# ESP-03_Breakout.net
KiCad netlist of a schematic drawn in EAGLE
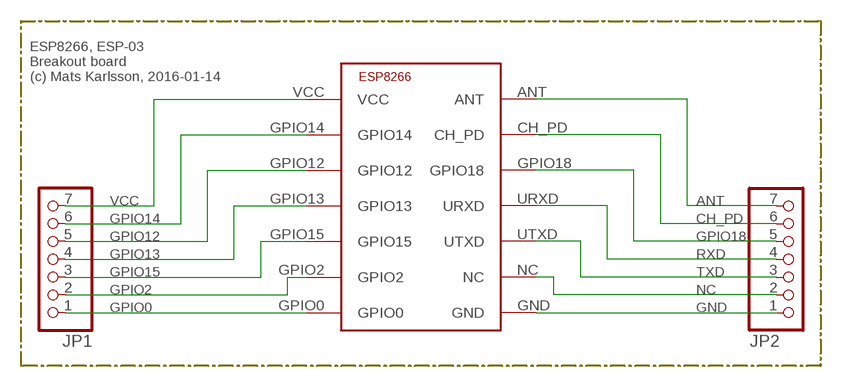
[diagram p0: schematic, sheet 1]

(export (version "E")
  (design (tool "Eeschema 10.0.6"))
  (components
    (comp (ref "JP1")
      (value "PINHD-1X71X07_SMT")
      (footprint "eagle-import:1X07_SMT")
      (libsource (lib "eagle-import") (part "PINHD-1X71X07_SMT"))
    )
    (comp (ref "JP2")
      (value "PINHD-1X71X07_SMT")
      (footprint "eagle-import:1X07_SMT")
      (libsource (lib "eagle-import") (part "PINHD-1X71X07_SMT"))
    )
    (comp (ref "U$1")
      (value "ESP8266-03")
      (footprint "eagle-import:ESP-03")
      (libsource (lib "eagle-import") (part "ESP8266-03"))
    )
  )
  (nets
    (net (code "1") (name "/ANT") (class "Default")
      (node (ref "JP2") (pin "7") (pinfunction "7_7") (pintype "passive"))
      (node (ref "U$1") (pin "ANT") (pinfunction "ANT_ANT") (pintype "bidirectional"))
    )
    (net (code "2") (name "/CH_PD") (class "Default")
      (node (ref "JP2") (pin "6") (pinfunction "6_6") (pintype "passive"))
      (node (ref "U$1") (pin "CH_PD") (pinfunction "CH_PD_CH_PD") (pintype "bidirectional"))
    )
    (net (code "3") (name "/GND") (class "Default")
      (node (ref "JP2") (pin "1") (pinfunction "1_1") (pintype "passive"))
      (node (ref "U$1") (pin "GND") (pinfunction "GND_GND") (pintype "bidirectional"))
    )
    (net (code "4") (name "/GPIO0") (class "Default")
      (node (ref "JP1") (pin "1") (pinfunction "1_1") (pintype "passive"))
      (node (ref "U$1") (pin "GPIO0") (pinfunction "GPIO0_GPIO0") (pintype "bidirectional"))
    )
    (net (code "5") (name "/GPIO2") (class "Default")
      (node (ref "JP1") (pin "2") (pinfunction "2_2") (pintype "passive"))
      (node (ref "U$1") (pin "GPIO2") (pinfunction "GPIO2_GPIO2") (pintype "bidirectional"))
    )
    (net (code "6") (name "/GPIO12") (class "Default")
      (node (ref "JP1") (pin "5") (pinfunction "5_5") (pintype "passive"))
      (node (ref "U$1") (pin "GPIO12") (pinfunction "GPIO12_GPIO12") (pintype "bidirectional"))
    )
    (net (code "7") (name "/GPIO13") (class "Default")
      (node (ref "JP1") (pin "4") (pinfunction "4_4") (pintype "passive"))
      (node (ref "U$1") (pin "GPIO13") (pinfunction "GPIO13_GPIO13") (pintype "bidirectional"))
    )
    (net (code "8") (name "/GPIO14") (class "Default")
      (node (ref "JP1") (pin "6") (pinfunction "6_6") (pintype "passive"))
      (node (ref "U$1") (pin "GPIO14") (pinfunction "GPIO14_GPIO14") (pintype "bidirectional"))
    )
    (net (code "9") (name "/GPIO15") (class "Default")
      (node (ref "JP1") (pin "3") (pinfunction "3_3") (pintype "passive"))
      (node (ref "U$1") (pin "GPIO15") (pinfunction "GPIO15_GPIO15") (pintype "bidirectional"))
    )
    (net (code "10") (name "/GPIO18") (class "Default")
      (node (ref "JP2") (pin "5") (pinfunction "5_5") (pintype "passive"))
      (node (ref "U$1") (pin "GPIO18") (pinfunction "GPIO18_GPIO18") (pintype "bidirectional"))
    )
    (net (code "11") (name "/NC") (class "Default")
      (node (ref "JP2") (pin "2") (pinfunction "2_2") (pintype "passive"))
      (node (ref "U$1") (pin "NC") (pinfunction "NC_NC") (pintype "bidirectional"))
    )
    (net (code "12") (name "/RXD") (class "Default")
      (node (ref "JP2") (pin "4") (pinfunction "4_4") (pintype "passive"))
      (node (ref "U$1") (pin "URXD") (pinfunction "URXD_URXD") (pintype "bidirectional"))
    )
    (net (code "13") (name "/TXD") (class "Default")
      (node (ref "JP2") (pin "3") (pinfunction "3_3") (pintype "passive"))
      (node (ref "U$1") (pin "UTXD") (pinfunction "UTXD_UTXD") (pintype "bidirectional"))
    )
    (net (code "14") (name "/VCC") (class "Default")
      (node (ref "JP1") (pin "7") (pinfunction "7_7") (pintype "passive"))
      (node (ref "U$1") (pin "VCC") (pinfunction "VCC_VCC") (pintype "bidirectional"))
    )
  )
)
